# 2_processor.net
KiCad netlist of a schematic drawn in Altium Designer
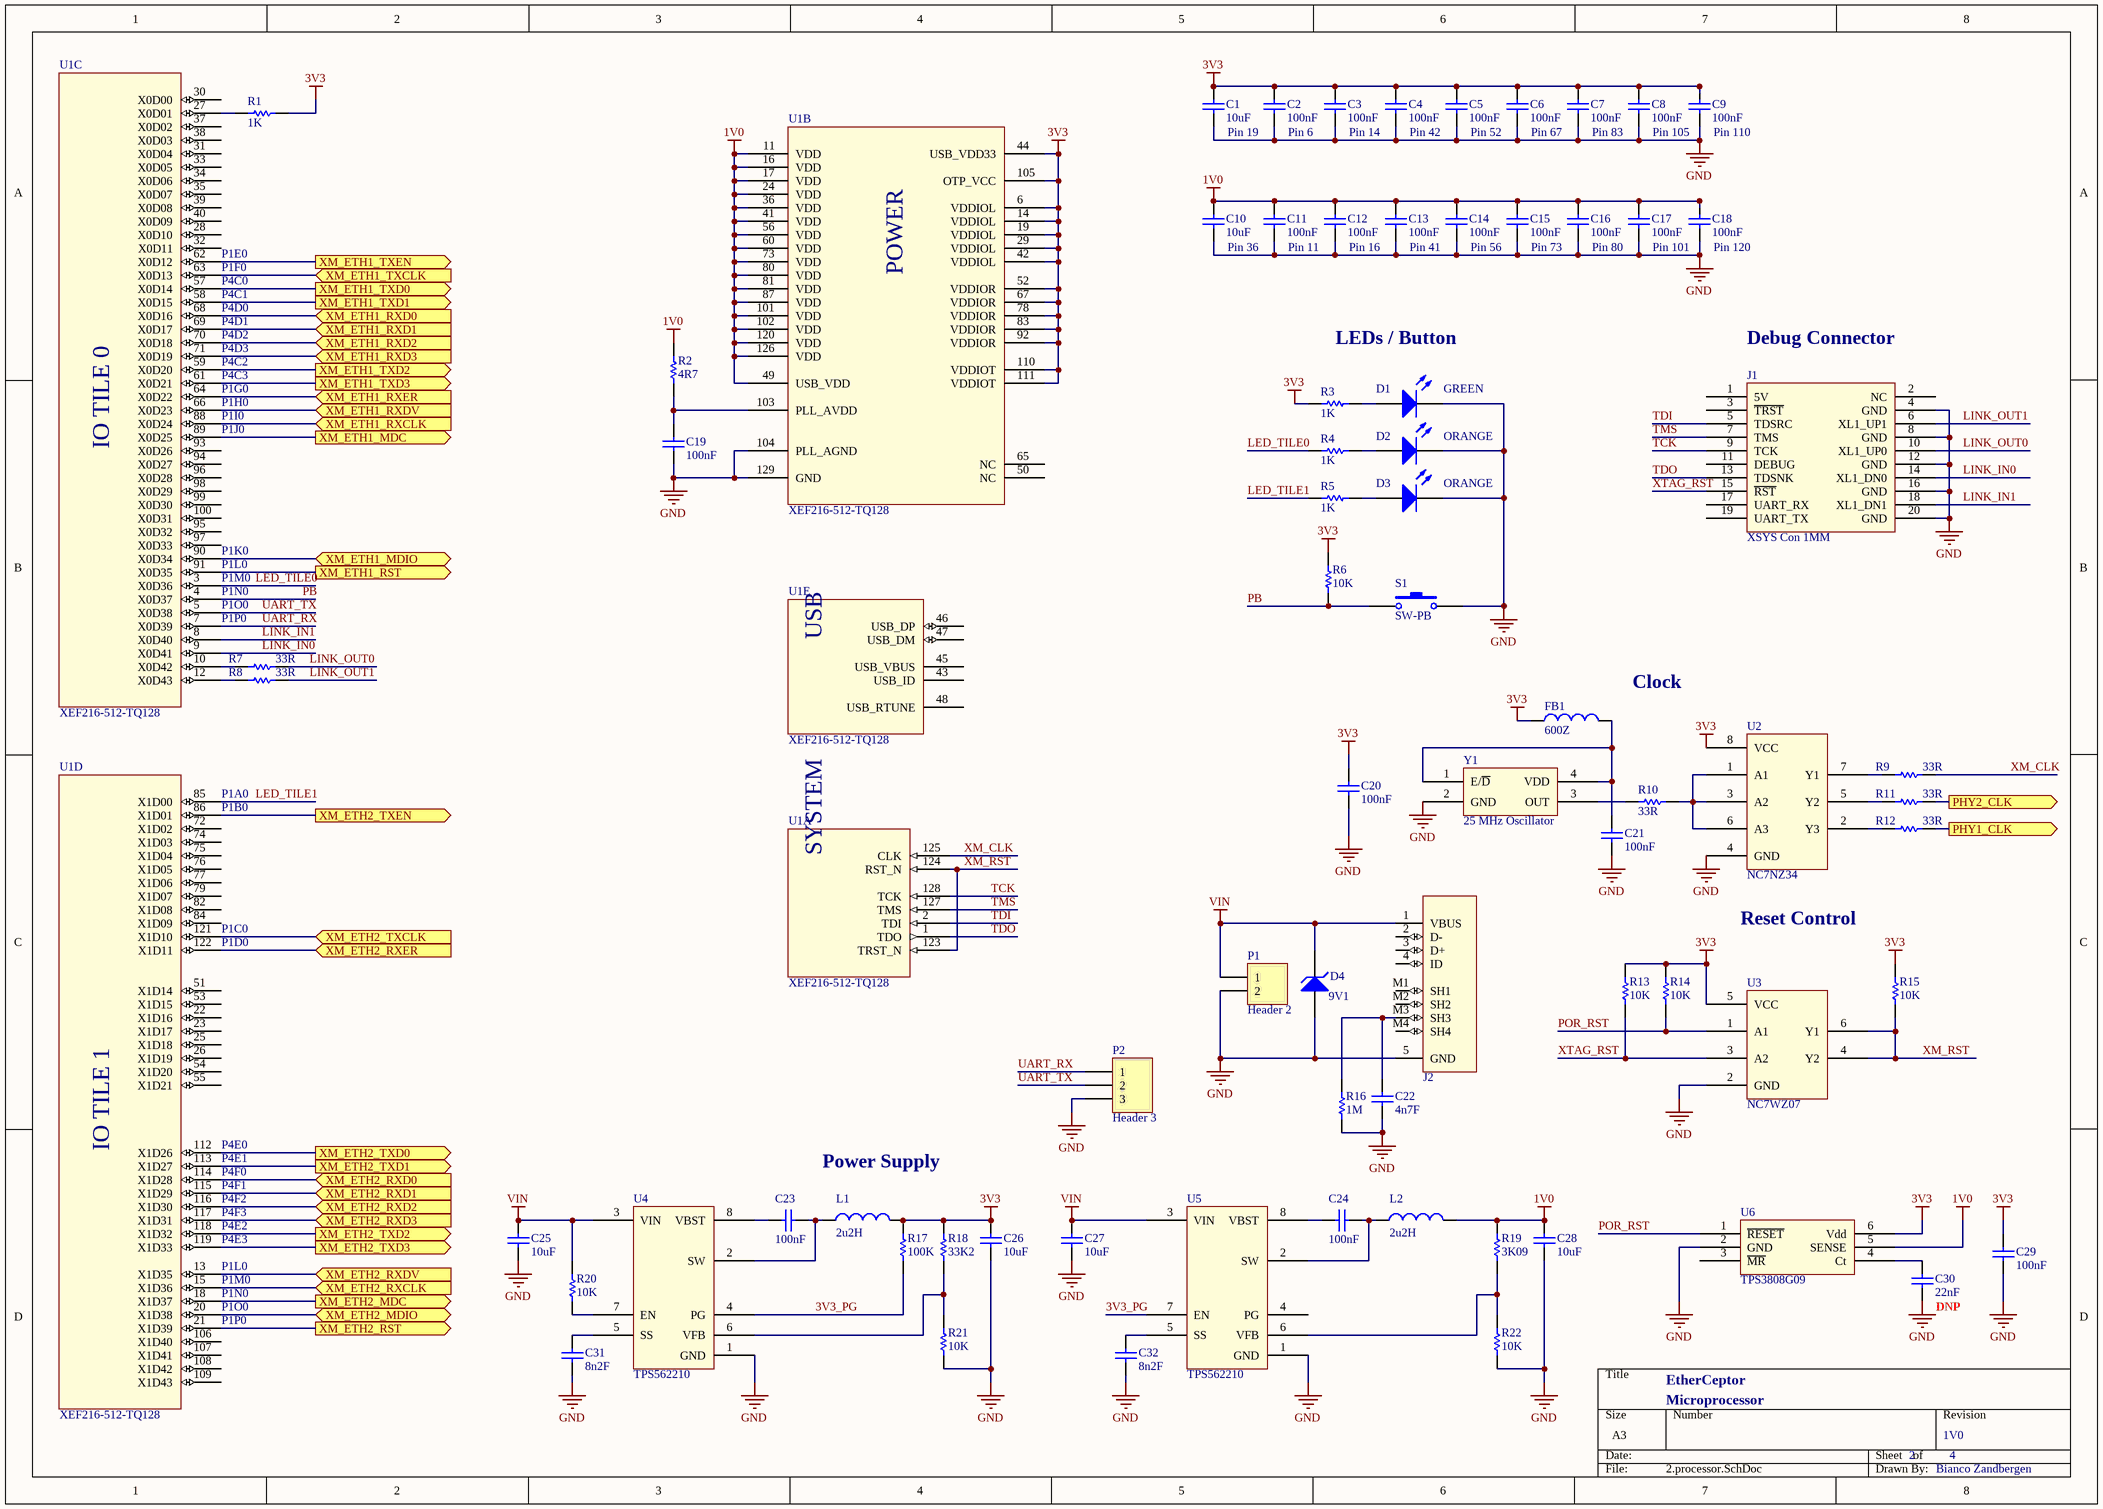
[diagram p0: 2.processor.SchDoc]

(export (version "E")
  (design (tool "Eeschema 10.0.6"))
  (components
    (comp (ref "C1")
      (value "Pin 19")
      (footprint "1608[0603]_CAP2")
      (description "Capacitor")
      (fields (field (name "ALTIUM_VALUE") "10uF") (field (name "MANUFACTURER") "SAMSUNG"))
      (libsource (lib "etherceptor") (part "Cap"))
    )
    (comp (ref "C2")
      (value "Pin 6")
      (footprint "1005[0402]_CAP2")
      (description "Capacitor")
      (fields (field (name "ALTIUM_VALUE") "100nF") (field (name "MANUFACTURER") "SAMSUNG"))
      (libsource (lib "etherceptor") (part "Cap"))
    )
    (comp (ref "C3")
      (value "Pin 14")
      (footprint "1005[0402]_CAP2")
      (description "Capacitor")
      (fields (field (name "ALTIUM_VALUE") "100nF") (field (name "MANUFACTURER") "SAMSUNG"))
      (libsource (lib "etherceptor") (part "Cap"))
    )
    (comp (ref "C4")
      (value "Pin 42")
      (footprint "1005[0402]_CAP2")
      (description "Capacitor")
      (fields (field (name "ALTIUM_VALUE") "100nF") (field (name "MANUFACTURER") "SAMSUNG"))
      (libsource (lib "etherceptor") (part "Cap"))
    )
    (comp (ref "C5")
      (value "Pin 52")
      (footprint "1005[0402]_CAP2")
      (description "Capacitor")
      (fields (field (name "ALTIUM_VALUE") "100nF") (field (name "MANUFACTURER") "SAMSUNG"))
      (libsource (lib "etherceptor") (part "Cap"))
    )
    (comp (ref "C6")
      (value "Pin 67")
      (footprint "1005[0402]_CAP2")
      (description "Capacitor")
      (fields (field (name "ALTIUM_VALUE") "100nF") (field (name "MANUFACTURER") "SAMSUNG"))
      (libsource (lib "etherceptor") (part "Cap"))
    )
    (comp (ref "C7")
      (value "Pin 83")
      (footprint "1005[0402]_CAP2")
      (description "Capacitor")
      (fields (field (name "ALTIUM_VALUE") "100nF") (field (name "MANUFACTURER") "SAMSUNG"))
      (libsource (lib "etherceptor") (part "Cap"))
    )
    (comp (ref "C8")
      (value "Pin 105")
      (footprint "1005[0402]_CAP2")
      (description "Capacitor")
      (fields (field (name "ALTIUM_VALUE") "100nF") (field (name "MANUFACTURER") "SAMSUNG"))
      (libsource (lib "etherceptor") (part "Cap"))
    )
    (comp (ref "C9")
      (value "Pin 110")
      (footprint "1005[0402]_CAP2")
      (description "Capacitor")
      (fields (field (name "ALTIUM_VALUE") "100nF") (field (name "MANUFACTURER") "SAMSUNG"))
      (libsource (lib "etherceptor") (part "Cap"))
    )
    (comp (ref "C10")
      (value "Pin 36")
      (footprint "1608[0603]_CAP2")
      (description "Capacitor")
      (fields (field (name "ALTIUM_VALUE") "10uF") (field (name "MANUFACTURER") "SAMSUNG"))
      (libsource (lib "etherceptor") (part "Cap"))
    )
    (comp (ref "C11")
      (value "Pin 11")
      (footprint "1005[0402]_CAP2")
      (description "Capacitor")
      (fields (field (name "ALTIUM_VALUE") "100nF") (field (name "MANUFACTURER") "SAMSUNG"))
      (libsource (lib "etherceptor") (part "Cap"))
    )
    (comp (ref "C12")
      (value "Pin 16")
      (footprint "1005[0402]_CAP2")
      (description "Capacitor")
      (fields (field (name "ALTIUM_VALUE") "100nF") (field (name "MANUFACTURER") "SAMSUNG"))
      (libsource (lib "etherceptor") (part "Cap"))
    )
    (comp (ref "C13")
      (value "Pin 41")
      (footprint "1005[0402]_CAP2")
      (description "Capacitor")
      (fields (field (name "ALTIUM_VALUE") "100nF") (field (name "MANUFACTURER") "SAMSUNG"))
      (libsource (lib "etherceptor") (part "Cap"))
    )
    (comp (ref "C14")
      (value "Pin 56")
      (footprint "1005[0402]_CAP2")
      (description "Capacitor")
      (fields (field (name "ALTIUM_VALUE") "100nF") (field (name "MANUFACTURER") "SAMSUNG"))
      (libsource (lib "etherceptor") (part "Cap"))
    )
    (comp (ref "C15")
      (value "Pin 73")
      (footprint "1005[0402]_CAP2")
      (description "Capacitor")
      (fields (field (name "ALTIUM_VALUE") "100nF") (field (name "MANUFACTURER") "SAMSUNG"))
      (libsource (lib "etherceptor") (part "Cap"))
    )
    (comp (ref "C16")
      (value "Pin 80")
      (footprint "1005[0402]_CAP2")
      (description "Capacitor")
      (fields (field (name "ALTIUM_VALUE") "100nF") (field (name "MANUFACTURER") "SAMSUNG"))
      (libsource (lib "etherceptor") (part "Cap"))
    )
    (comp (ref "C17")
      (value "Pin 101")
      (footprint "1005[0402]_CAP2")
      (description "Capacitor")
      (fields (field (name "ALTIUM_VALUE") "100nF") (field (name "MANUFACTURER") "SAMSUNG"))
      (libsource (lib "etherceptor") (part "Cap"))
    )
    (comp (ref "C18")
      (value "Pin 120")
      (footprint "1005[0402]_CAP2")
      (description "Capacitor")
      (fields (field (name "ALTIUM_VALUE") "100nF") (field (name "MANUFACTURER") "SAMSUNG"))
      (libsource (lib "etherceptor") (part "Cap"))
    )
    (comp (ref "C19")
      (value "100nF")
      (footprint "1005[0402]_CAP2")
      (description "Capacitor")
      (fields (field (name "MANUFACTURER") "SAMSUNG") (field (name "Comment") "Cap"))
      (libsource (lib "etherceptor") (part "Cap"))
    )
    (comp (ref "C20")
      (value "100nF")
      (footprint "1005[0402]_CAP2")
      (description "Capacitor")
      (fields (field (name "MANUFACTURER") "SAMSUNG") (field (name "Comment") "Cap"))
      (libsource (lib "etherceptor") (part "Cap"))
    )
    (comp (ref "C21")
      (value "100nF")
      (footprint "1005[0402]_CAP2")
      (description "Capacitor")
      (fields (field (name "MANUFACTURER") "SAMSUNG") (field (name "Comment") "Cap"))
      (libsource (lib "etherceptor") (part "Cap"))
    )
    (comp (ref "C22")
      (value "4n7F")
      (footprint "1005[0402]_CAP2")
      (description "Capacitor")
      (fields (field (name "MANUFACTURER") "SAMSUNG") (field (name "Comment") "Cap"))
      (libsource (lib "etherceptor") (part "Cap"))
    )
    (comp (ref "C23")
      (value "100nF")
      (footprint "1005[0402]_CAP2")
      (description "Capacitor")
      (fields (field (name "MANUFACTURER") "SAMSUNG") (field (name "Comment") "Cap"))
      (libsource (lib "etherceptor") (part "Cap"))
    )
    (comp (ref "C24")
      (value "100nF")
      (footprint "1005[0402]_CAP2")
      (description "Capacitor")
      (fields (field (name "MANUFACTURER") "SAMSUNG") (field (name "Comment") "Cap"))
      (libsource (lib "etherceptor") (part "Cap"))
    )
    (comp (ref "C25")
      (value "10uF")
      (footprint "1608[0603]_CAP2")
      (description "Capacitor")
      (fields (field (name "MANUFACTURER") "SAMSUNG") (field (name "Comment") "Cap"))
      (libsource (lib "etherceptor") (part "Cap"))
    )
    (comp (ref "C26")
      (value "10uF")
      (footprint "1608[0603]_CAP2")
      (description "Capacitor")
      (fields (field (name "MANUFACTURER") "SAMSUNG") (field (name "Comment") "Cap"))
      (libsource (lib "etherceptor") (part "Cap"))
    )
    (comp (ref "C27")
      (value "10uF")
      (footprint "1608[0603]_CAP2")
      (description "Capacitor")
      (fields (field (name "MANUFACTURER") "SAMSUNG") (field (name "Comment") "Cap"))
      (libsource (lib "etherceptor") (part "Cap"))
    )
    (comp (ref "C28")
      (value "10uF")
      (footprint "1608[0603]_CAP2")
      (description "Capacitor")
      (fields (field (name "MANUFACTURER") "SAMSUNG") (field (name "Comment") "Cap"))
      (libsource (lib "etherceptor") (part "Cap"))
    )
    (comp (ref "C29")
      (value "100nF")
      (footprint "1005[0402]_CAP2")
      (description "Capacitor")
      (fields (field (name "MANUFACTURER") "SAMSUNG") (field (name "Comment") "Cap"))
      (libsource (lib "etherceptor") (part "Cap"))
    )
    (comp (ref "C30")
      (value "22nF")
      (footprint "1005[0402]_CAP2")
      (description "Capacitor")
      (fields (field (name "MANUFACTURER") "SAMSUNG") (field (name "Comment") "Cap"))
      (libsource (lib "etherceptor") (part "Cap"))
    )
    (comp (ref "C31")
      (value "8n2F")
      (footprint "1005[0402]_CAP2")
      (description "Capacitor")
      (fields (field (name "MANUFACTURER") "SAMSUNG") (field (name "Comment") "Cap"))
      (libsource (lib "etherceptor") (part "Cap"))
    )
    (comp (ref "C32")
      (value "8n2F")
      (footprint "1005[0402]_CAP2")
      (description "Capacitor")
      (fields (field (name "MANUFACTURER") "SAMSUNG") (field (name "Comment") "Cap"))
      (libsource (lib "etherceptor") (part "Cap"))
    )
    (comp (ref "D1")
      (value "GREEN")
      (footprint "1608[0603]_LED")
      (description "SMD LED")
      (fields (field (name "MANUFACTURER") "BROADCOM") (field (name "Comment") "LED3"))
      (libsource (lib "etherceptor") (part "LED3"))
    )
    (comp (ref "D2")
      (value "ORANGE")
      (footprint "1608[0603]_LED")
      (description "SMD LED")
      (fields (field (name "MANUFACTURER") "BROADCOM") (field (name "Comment") "LED3"))
      (libsource (lib "etherceptor") (part "LED3"))
    )
    (comp (ref "D3")
      (value "ORANGE")
      (footprint "1608[0603]_LED")
      (description "SMD LED")
      (fields (field (name "MANUFACTURER") "BROADCOM") (field (name "Comment") "LED3"))
      (libsource (lib "etherceptor") (part "LED3"))
    )
    (comp (ref "D4")
      (value "9V1")
      (footprint "SOD123F")
      (description "Zener Diode")
      (fields (field (name "MANUFACTURER") "NEXPERIA"))
      (libsource (lib "etherceptor") (part "Diode Zener"))
    )
    (comp (ref "FB1")
      (value "600Z")
      (footprint "1005[0402]_FB2")
      (description "Ferrite Bead")
      (fields (field (name "MANUFACTURER") "MURATA"))
      (libsource (lib "etherceptor") (part "Ferrite Bead"))
    )
    (comp (ref "J1")
      (value "XSYS Con 1MM")
      (footprint "M40-3201045R")
      (description "XTAG2 Connector")
      (fields (field (name "MANUFACTURER") "HARWIN"))
      (libsource (lib "etherceptor") (part "XTAG2_CON"))
    )
    (comp (ref "J2")
      (value "Micro-USB B Receptacle")
      (footprint "MOLEX_105017-0001")
      (description "Micro-USB B Receptacle with Flange, Bottom Mount, SMT, Lead-Free")
      (fields (field (name "MP") "47346-0001") (field (name "MF") "Molex"))
      (libsource (lib "etherceptor") (part "Molex Micro-USB 105017-1001"))
    )
    (comp (ref "L1")
      (value "2u2H")
      (footprint "2012[0805]_IND")
      (description "Inductor")
      (fields (field (name "MANUFACTURER") "WURTH"))
      (libsource (lib "etherceptor") (part "Inductor"))
    )
    (comp (ref "L2")
      (value "2u2H")
      (footprint "2012[0805]_IND")
      (description "Inductor")
      (fields (field (name "MANUFACTURER") "WURTH"))
      (libsource (lib "etherceptor") (part "Inductor"))
    )
    (comp (ref "P1")
      (value "Header 2")
      (footprint "HDR1X2")
      (description "Header, 2-Pin")
      (libsource (lib "etherceptor") (part "Header 2"))
    )
    (comp (ref "P2")
      (value "Header 3")
      (footprint "HDR1X3")
      (description "Header, 3-Pin")
      (libsource (lib "etherceptor") (part "Header 3"))
    )
    (comp (ref "R1")
      (value "1K")
      (footprint "1005[0402]_RES2")
      (description "Resistor")
      (fields (field (name "MANUFACTURER") "PANASONIC") (field (name "Comment") "Res"))
      (libsource (lib "etherceptor") (part "Res"))
    )
    (comp (ref "R2")
      (value "4R7")
      (footprint "1005[0402]_RES2")
      (description "Resistor")
      (fields (field (name "MANUFACTURER") "PANASONIC") (field (name "Comment") "Res"))
      (libsource (lib "etherceptor") (part "Res"))
    )
    (comp (ref "R3")
      (value "1K")
      (footprint "1005[0402]_RES2")
      (description "Resistor")
      (fields (field (name "MANUFACTURER") "PANASONIC") (field (name "Comment") "Res"))
      (libsource (lib "etherceptor") (part "Res"))
    )
    (comp (ref "R4")
      (value "1K")
      (footprint "1005[0402]_RES2")
      (description "Resistor")
      (fields (field (name "MANUFACTURER") "PANASONIC") (field (name "Comment") "Res"))
      (libsource (lib "etherceptor") (part "Res"))
    )
    (comp (ref "R5")
      (value "1K")
      (footprint "1005[0402]_RES2")
      (description "Resistor")
      (fields (field (name "MANUFACTURER") "PANASONIC") (field (name "Comment") "Res"))
      (libsource (lib "etherceptor") (part "Res"))
    )
    (comp (ref "R6")
      (value "10K")
      (footprint "1005[0402]_RES2")
      (description "Resistor")
      (fields (field (name "MANUFACTURER") "PANASONIC") (field (name "Comment") "Res"))
      (libsource (lib "etherceptor") (part "Res"))
    )
    (comp (ref "R7")
      (value "33R")
      (footprint "1005[0402]_RES2")
      (description "Resistor")
      (fields (field (name "MANUFACTURER") "PANASONIC") (field (name "Comment") "Res"))
      (libsource (lib "etherceptor") (part "Res"))
    )
    (comp (ref "R8")
      (value "33R")
      (footprint "1005[0402]_RES2")
      (description "Resistor")
      (fields (field (name "MANUFACTURER") "PANASONIC") (field (name "Comment") "Res"))
      (libsource (lib "etherceptor") (part "Res"))
    )
    (comp (ref "R9")
      (value "33R")
      (footprint "1005[0402]_RES2")
      (description "Resistor")
      (fields (field (name "MANUFACTURER") "PANASONIC") (field (name "Comment") "Res"))
      (libsource (lib "etherceptor") (part "Res"))
    )
    (comp (ref "R10")
      (value "33R")
      (footprint "1005[0402]_RES2")
      (description "Resistor")
      (fields (field (name "MANUFACTURER") "PANASONIC") (field (name "Comment") "Res"))
      (libsource (lib "etherceptor") (part "Res"))
    )
    (comp (ref "R11")
      (value "33R")
      (footprint "1005[0402]_RES2")
      (description "Resistor")
      (fields (field (name "MANUFACTURER") "PANASONIC") (field (name "Comment") "Res"))
      (libsource (lib "etherceptor") (part "Res"))
    )
    (comp (ref "R12")
      (value "33R")
      (footprint "1005[0402]_RES2")
      (description "Resistor")
      (fields (field (name "MANUFACTURER") "PANASONIC") (field (name "Comment") "Res"))
      (libsource (lib "etherceptor") (part "Res"))
    )
    (comp (ref "R13")
      (value "10K")
      (footprint "1005[0402]_RES2")
      (description "Resistor")
      (fields (field (name "MANUFACTURER") "PANASONIC") (field (name "Comment") "Res"))
      (libsource (lib "etherceptor") (part "Res"))
    )
    (comp (ref "R14")
      (value "10K")
      (footprint "1005[0402]_RES2")
      (description "Resistor")
      (fields (field (name "MANUFACTURER") "PANASONIC") (field (name "Comment") "Res"))
      (libsource (lib "etherceptor") (part "Res"))
    )
    (comp (ref "R15")
      (value "10K")
      (footprint "1005[0402]_RES2")
      (description "Resistor")
      (fields (field (name "MANUFACTURER") "PANASONIC") (field (name "Comment") "Res"))
      (libsource (lib "etherceptor") (part "Res"))
    )
    (comp (ref "R16")
      (value "1M")
      (footprint "1005[0402]_RES2")
      (description "Resistor")
      (fields (field (name "MANUFACTURER") "PANASONIC") (field (name "Comment") "Res"))
      (libsource (lib "etherceptor") (part "Res"))
    )
    (comp (ref "R17")
      (value "100K")
      (footprint "1005[0402]_RES2")
      (description "Resistor")
      (fields (field (name "MANUFACTURER") "PANASONIC") (field (name "Comment") "Res"))
      (libsource (lib "etherceptor") (part "Res"))
    )
    (comp (ref "R18")
      (value "33K2")
      (footprint "1005[0402]_RES2")
      (description "Resistor")
      (fields (field (name "MANUFACTURER") "PANASONIC") (field (name "Comment") "Res"))
      (libsource (lib "etherceptor") (part "Res"))
    )
    (comp (ref "R19")
      (value "3K09")
      (footprint "1005[0402]_RES2")
      (description "Resistor")
      (fields (field (name "MANUFACTURER") "PANASONIC") (field (name "Comment") "Res"))
      (libsource (lib "etherceptor") (part "Res"))
    )
    (comp (ref "R20")
      (value "10K")
      (footprint "1005[0402]_RES2")
      (description "Resistor")
      (fields (field (name "MANUFACTURER") "PANASONIC") (field (name "Comment") "Res"))
      (libsource (lib "etherceptor") (part "Res"))
    )
    (comp (ref "R21")
      (value "10K")
      (footprint "1005[0402]_RES2")
      (description "Resistor")
      (fields (field (name "MANUFACTURER") "PANASONIC") (field (name "Comment") "Res"))
      (libsource (lib "etherceptor") (part "Res"))
    )
    (comp (ref "R22")
      (value "10K")
      (footprint "1005[0402]_RES2")
      (description "Resistor")
      (fields (field (name "MANUFACTURER") "PANASONIC") (field (name "Comment") "Res"))
      (libsource (lib "etherceptor") (part "Res"))
    )
    (comp (ref "S1")
      (value "SW-PB")
      (footprint "TACTILE_SW_6035_1")
      (description "Switch")
      (fields (field (name "MANUFACTURER") "PANASONIC"))
      (libsource (lib "etherceptor") (part "SW-PB"))
    )
    (comp (ref "U1")
      (value "XEF216-512-TQ128")
      (footprint "XMOS_LQFP_128_XEF216_512")
      (description "XMOS xCORE200 Processor")
      (fields
        (field (name "MANUFACTURER") "XMOS")
        (field (name "MANUFACTURER PART NUMBER") "XE216-512-TQ128")
      )
      (libsource (lib "etherceptor") (part "XEF216-512-TQ128"))
    )
    (comp (ref "U2")
      (value "NC7NZ34")
      (footprint "US8")
      (description "Tripple Buffer")
      (fields (field (name "MANUFACTURER") "ON SEMICONDUCTOR"))
      (libsource (lib "etherceptor") (part "NC7NZ34"))
    )
    (comp (ref "U3")
      (value "NC7WZ07")
      (footprint "SOT363-6M_SC70")
      (description "Dual Buffer (open drain output)")
      (fields (field (name "MANUFACTURER") "ON SEMICONDUCTOR"))
      (libsource (lib "etherceptor") (part "NC7WZ07"))
    )
    (comp (ref "U4")
      (value "TPS562210")
      (footprint "SOT-23-8")
      (description "Buck converter")
      (fields (field (name "MANUFACTURER") "TEXAS INSTRUMENTS"))
      (libsource (lib "etherceptor") (part "TPS562210"))
    )
    (comp (ref "U5")
      (value "TPS562210")
      (footprint "SOT-23-8")
      (description "Buck converter")
      (fields (field (name "MANUFACTURER") "TEXAS INSTRUMENTS"))
      (libsource (lib "etherceptor") (part "TPS562210"))
    )
    (comp (ref "U6")
      (value "TPS3808G09")
      (footprint "SOT23-6")
      (description "Power on Reset controller 0.9V")
      (fields (field (name "MANUFACTURER") "TEXAS INSTRUMENTS"))
      (libsource (lib "etherceptor") (part "TPS3808G09"))
    )
    (comp (ref "Y1")
      (value "25 MHz Oscillator")
      (footprint "OSC_32_25")
      (description "Crystal Oscillator")
      (fields (field (name "MANUFACTURER") "ABRACON"))
      (libsource (lib "etherceptor") (part "oscillator"))
    )
  )
  (nets
    (net (code "1") (name "/3V3_PG") (class "Default")
      (node (ref "R17") (pin "1") (pinfunction "1_1") (pintype "passive"))
      (node (ref "U4") (pin "4") (pinfunction "PG_4") (pintype "passive"))
      (node (ref "U5") (pin "7") (pinfunction "EN_7") (pintype "passive"))
    )
    (net (code "2") (name "/LED_TILE0") (class "Default")
      (node (ref "R4") (pin "2") (pinfunction "2_2") (pintype "passive"))
      (node (ref "U1") (pin "3") (pinfunction "X0D36_3") (pintype "bidirectional"))
    )
    (net (code "3") (name "/LED_TILE1") (class "Default")
      (node (ref "R5") (pin "2") (pinfunction "2_2") (pintype "passive"))
      (node (ref "U1") (pin "85") (pinfunction "X1D00_85") (pintype "bidirectional"))
    )
    (net (code "4") (name "/LINK_IN0") (class "Default")
      (node (ref "J1") (pin "14") (pinfunction "XL1_DN0_14") (pintype "passive"))
      (node (ref "U1") (pin "9") (pinfunction "X0D41_9") (pintype "bidirectional"))
    )
    (net (code "5") (name "/LINK_IN1") (class "Default")
      (node (ref "J1") (pin "18") (pinfunction "XL1_DN1_18") (pintype "passive"))
      (node (ref "U1") (pin "8") (pinfunction "X0D40_8") (pintype "bidirectional"))
    )
    (net (code "6") (name "/LINK_OUT0") (class "Default")
      (node (ref "J1") (pin "10") (pinfunction "XL1_UP0_10") (pintype "passive"))
      (node (ref "R7") (pin "1") (pinfunction "1_1") (pintype "passive"))
    )
    (net (code "7") (name "/LINK_OUT1") (class "Default")
      (node (ref "J1") (pin "6") (pinfunction "XL1_UP1_6") (pintype "passive"))
      (node (ref "R8") (pin "1") (pinfunction "1_1") (pintype "passive"))
    )
    (net (code "8") (name "/PB") (class "Default")
      (node (ref "R6") (pin "1") (pinfunction "1_1") (pintype "passive"))
      (node (ref "S1") (pin "1") (pinfunction "1_1") (pintype "passive"))
      (node (ref "U1") (pin "4") (pinfunction "X0D37_4") (pintype "bidirectional"))
    )
    (net (code "9") (name "/PHY1_CLK") (class "Default")
      (node (ref "R12") (pin "1") (pinfunction "1_1") (pintype "passive"))
    )
    (net (code "10") (name "/PHY2_CLK") (class "Default")
      (node (ref "R11") (pin "1") (pinfunction "1_1") (pintype "passive"))
    )
    (net (code "11") (name "/POR_RST") (class "Default")
      (node (ref "R14") (pin "1") (pinfunction "1_1") (pintype "passive"))
      (node (ref "U3") (pin "1") (pinfunction "A1_1") (pintype "passive"))
      (node (ref "U6") (pin "1") (pinfunction "~{RESET}_1") (pintype "passive"))
    )
    (net (code "12") (name "/TCK") (class "Default")
      (node (ref "J1") (pin "9") (pinfunction "TCK_9") (pintype "passive"))
      (node (ref "U1") (pin "128") (pinfunction "TCK_128") (pintype "input"))
    )
    (net (code "13") (name "/TDI") (class "Default")
      (node (ref "J1") (pin "5") (pinfunction "TDSRC_5") (pintype "passive"))
      (node (ref "U1") (pin "2") (pinfunction "TDI_2") (pintype "input"))
    )
    (net (code "14") (name "/TDO") (class "Default")
      (node (ref "J1") (pin "13") (pinfunction "TDSNK_13") (pintype "passive"))
      (node (ref "U1") (pin "1") (pinfunction "TDO_1") (pintype "output"))
    )
    (net (code "15") (name "/TMS") (class "Default")
      (node (ref "J1") (pin "7") (pinfunction "TMS_7") (pintype "passive"))
      (node (ref "U1") (pin "127") (pinfunction "TMS_127") (pintype "input"))
    )
    (net (code "16") (name "/UART_RX") (class "Default")
      (node (ref "P2") (pin "1") (pinfunction "1_1") (pintype "passive"))
      (node (ref "U1") (pin "7") (pinfunction "X0D39_7") (pintype "bidirectional"))
    )
    (net (code "17") (name "/UART_TX") (class "Default")
      (node (ref "P2") (pin "2") (pinfunction "2_2") (pintype "passive"))
      (node (ref "U1") (pin "5") (pinfunction "X0D38_5") (pintype "bidirectional"))
    )
    (net (code "18") (name "/XM_CLK") (class "Default")
      (node (ref "R9") (pin "1") (pinfunction "1_1") (pintype "passive"))
      (node (ref "U1") (pin "125") (pinfunction "CLK_125") (pintype "input"))
    )
    (net (code "19") (name "/XM_ETH1_MDC") (class "Default")
      (node (ref "U1") (pin "89") (pinfunction "X0D25_89") (pintype "bidirectional"))
    )
    (net (code "20") (name "/XM_ETH1_MDIO") (class "Default")
      (node (ref "U1") (pin "90") (pinfunction "X0D34_90") (pintype "bidirectional"))
    )
    (net (code "21") (name "/XM_ETH1_RST") (class "Default")
      (node (ref "U1") (pin "91") (pinfunction "X0D35_91") (pintype "bidirectional"))
    )
    (net (code "22") (name "/XM_ETH1_RXCLK") (class "Default")
      (node (ref "U1") (pin "88") (pinfunction "X0D24_88") (pintype "bidirectional"))
    )
    (net (code "23") (name "/XM_ETH1_RXD0") (class "Default")
      (node (ref "U1") (pin "68") (pinfunction "X0D16_68") (pintype "bidirectional"))
    )
    (net (code "24") (name "/XM_ETH1_RXD1") (class "Default")
      (node (ref "U1") (pin "69") (pinfunction "X0D17_69") (pintype "bidirectional"))
    )
    (net (code "25") (name "/XM_ETH1_RXD2") (class "Default")
      (node (ref "U1") (pin "70") (pinfunction "X0D18_70") (pintype "bidirectional"))
    )
    (net (code "26") (name "/XM_ETH1_RXD3") (class "Default")
      (node (ref "U1") (pin "71") (pinfunction "X0D19_71") (pintype "bidirectional"))
    )
    (net (code "27") (name "/XM_ETH1_RXDV") (class "Default")
      (node (ref "U1") (pin "66") (pinfunction "X0D23_66") (pintype "bidirectional"))
    )
    (net (code "28") (name "/XM_ETH1_RXER") (class "Default")
      (node (ref "U1") (pin "64") (pinfunction "X0D22_64") (pintype "bidirectional"))
    )
    (net (code "29") (name "/XM_ETH1_TXCLK") (class "Default")
      (node (ref "U1") (pin "63") (pinfunction "X0D13_63") (pintype "bidirectional"))
    )
    (net (code "30") (name "/XM_ETH1_TXD0") (class "Default")
      (node (ref "U1") (pin "57") (pinfunction "X0D14_57") (pintype "bidirectional"))
    )
    (net (code "31") (name "/XM_ETH1_TXD1") (class "Default")
      (node (ref "U1") (pin "58") (pinfunction "X0D15_58") (pintype "bidirectional"))
    )
    (net (code "32") (name "/XM_ETH1_TXD2") (class "Default")
      (node (ref "U1") (pin "59") (pinfunction "X0D20_59") (pintype "bidirectional"))
    )
    (net (code "33") (name "/XM_ETH1_TXD3") (class "Default")
      (node (ref "U1") (pin "61") (pinfunction "X0D21_61") (pintype "bidirectional"))
    )
    (net (code "34") (name "/XM_ETH1_TXEN") (class "Default")
      (node (ref "U1") (pin "62") (pinfunction "X0D12_62") (pintype "bidirectional"))
    )
    (net (code "35") (name "/XM_ETH2_MDC") (class "Default")
      (node (ref "U1") (pin "18") (pinfunction "X1D37_18") (pintype "bidirectional"))
    )
    (net (code "36") (name "/XM_ETH2_MDIO") (class "Default")
      (node (ref "U1") (pin "20") (pinfunction "X1D38_20") (pintype "bidirectional"))
    )
    (net (code "37") (name "/XM_ETH2_RST") (class "Default")
      (node (ref "U1") (pin "21") (pinfunction "X1D39_21") (pintype "bidirectional"))
    )
    (net (code "38") (name "/XM_ETH2_RXCLK") (class "Default")
      (node (ref "U1") (pin "15") (pinfunction "X1D36_15") (pintype "bidirectional"))
    )
    (net (code "39") (name "/XM_ETH2_RXD0") (class "Default")
      (node (ref "U1") (pin "114") (pinfunction "X1D28_114") (pintype "bidirectional"))
    )
    (net (code "40") (name "/XM_ETH2_RXD1") (class "Default")
      (node (ref "U1") (pin "115") (pinfunction "X1D29_115") (pintype "bidirectional"))
    )
    (net (code "41") (name "/XM_ETH2_RXD2") (class "Default")
      (node (ref "U1") (pin "116") (pinfunction "X1D30_116") (pintype "bidirectional"))
    )
    (net (code "42") (name "/XM_ETH2_RXD3") (class "Default")
      (node (ref "U1") (pin "117") (pinfunction "X1D31_117") (pintype "bidirectional"))
    )
    (net (code "43") (name "/XM_ETH2_RXDV") (class "Default")
      (node (ref "U1") (pin "13") (pinfunction "X1D35_13") (pintype "bidirectional"))
    )
    (net (code "44") (name "/XM_ETH2_RXER") (class "Default")
      (node (ref "U1") (pin "122") (pinfunction "X1D11_122") (pintype "bidirectional"))
    )
    (net (code "45") (name "/XM_ETH2_TXCLK") (class "Default")
      (node (ref "U1") (pin "121") (pinfunction "X1D10_121") (pintype "bidirectional"))
    )
    (net (code "46") (name "/XM_ETH2_TXD0") (class "Default")
      (node (ref "U1") (pin "112") (pinfunction "X1D26_112") (pintype "bidirectional"))
    )
    (net (code "47") (name "/XM_ETH2_TXD1") (class "Default")
      (node (ref "U1") (pin "113") (pinfunction "X1D27_113") (pintype "bidirectional"))
    )
    (net (code "48") (name "/XM_ETH2_TXD2") (class "Default")
      (node (ref "U1") (pin "118") (pinfunction "X1D32_118") (pintype "bidirectional"))
    )
    (net (code "49") (name "/XM_ETH2_TXD3") (class "Default")
      (node (ref "U1") (pin "119") (pinfunction "X1D33_119") (pintype "bidirectional"))
    )
    (net (code "50") (name "/XM_ETH2_TXEN") (class "Default")
      (node (ref "U1") (pin "86") (pinfunction "X1D01_86") (pintype "bidirectional"))
    )
    (net (code "51") (name "/XM_RST") (class "Default")
      (node (ref "R15") (pin "1") (pinfunction "1_1") (pintype "passive"))
      (node (ref "U1") (pin "123") (pinfunction "TRST_N_123") (pintype "input"))
      (node (ref "U1") (pin "124") (pinfunction "RST_N_124") (pintype "input"))
      (node (ref "U3") (pin "4") (pinfunction "Y2_4") (pintype "passive"))
      (node (ref "U3") (pin "6") (pinfunction "Y1_6") (pintype "passive"))
    )
    (net (code "52") (name "/XTAG_RST") (class "Default")
      (node (ref "J1") (pin "15") (pinfunction "~{RST}_15") (pintype "passive"))
      (node (ref "R13") (pin "1") (pinfunction "1_1") (pintype "passive"))
      (node (ref "U3") (pin "3") (pinfunction "A2_3") (pintype "passive"))
    )
    (net (code "53") (name "1V0") (class "Default")
      (node (ref "C10") (pin "2") (pinfunction "2_2") (pintype "passive"))
      (node (ref "C11") (pin "2") (pinfunction "2_2") (pintype "passive"))
      (node (ref "C12") (pin "2") (pinfunction "2_2") (pintype "passive"))
      (node (ref "C13") (pin "2") (pinfunction "2_2") (pintype "passive"))
      (node (ref "C14") (pin "2") (pinfunction "2_2") (pintype "passive"))
      (node (ref "C15") (pin "2") (pinfunction "2_2") (pintype "passive"))
      (node (ref "C16") (pin "2") (pinfunction "2_2") (pintype "passive"))
      (node (ref "C17") (pin "2") (pinfunction "2_2") (pintype "passive"))
      (node (ref "C18") (pin "2") (pinfunction "2_2") (pintype "passive"))
      (node (ref "C28") (pin "2") (pinfunction "2_2") (pintype "passive"))
      (node (ref "L2") (pin "2") (pinfunction "2_2") (pintype "passive"))
      (node (ref "R19") (pin "2") (pinfunction "2_2") (pintype "passive"))
      (node (ref "R2") (pin "2") (pinfunction "2_2") (pintype "passive"))
      (node (ref "U1") (pin "101") (pinfunction "VDD_101") (pintype "power_in"))
      (node (ref "U1") (pin "102") (pinfunction "VDD_102") (pintype "power_in"))
      (node (ref "U1") (pin "11") (pinfunction "VDD_11") (pintype "power_in"))
      (node (ref "U1") (pin "120") (pinfunction "VDD_120") (pintype "power_in"))
      (node (ref "U1") (pin "126") (pinfunction "VDD_126") (pintype "power_in"))
      (node (ref "U1") (pin "16") (pinfunction "VDD_16") (pintype "power_in"))
      (node (ref "U1") (pin "17") (pinfunction "VDD_17") (pintype "power_in"))
      (node (ref "U1") (pin "24") (pinfunction "VDD_24") (pintype "power_in"))
      (node (ref "U1") (pin "36") (pinfunction "VDD_36") (pintype "power_in"))
      (node (ref "U1") (pin "41") (pinfunction "VDD_41") (pintype "power_in"))
      (node (ref "U1") (pin "49") (pinfunction "USB_VDD_49") (pintype "power_in"))
      (node (ref "U1") (pin "56") (pinfunction "VDD_56") (pintype "power_in"))
      (node (ref "U1") (pin "60") (pinfunction "VDD_60") (pintype "power_in"))
      (node (ref "U1") (pin "73") (pinfunction "VDD_73") (pintype "power_in"))
      (node (ref "U1") (pin "80") (pinfunction "VDD_80") (pintype "power_in"))
      (node (ref "U1") (pin "81") (pinfunction "VDD_81") (pintype "power_in"))
      (node (ref "U1") (pin "87") (pinfunction "VDD_87") (pintype "power_in"))
      (node (ref "U6") (pin "5") (pinfunction "SENSE_5") (pintype "passive"))
    )
    (net (code "54") (name "3V3") (class "Default")
      (node (ref "C1") (pin "2") (pinfunction "2_2") (pintype "passive"))
      (node (ref "C2") (pin "2") (pinfunction "2_2") (pintype "passive"))
      (node (ref "C20") (pin "2") (pinfunction "2_2") (pintype "passive"))
      (node (ref "C26") (pin "2") (pinfunction "2_2") (pintype "passive"))
      (node (ref "C29") (pin "2") (pinfunction "2_2") (pintype "passive"))
      (node (ref "C3") (pin "2") (pinfunction "2_2") (pintype "passive"))
      (node (ref "C4") (pin "2") (pinfunction "2_2") (pintype "passive"))
      (node (ref "C5") (pin "2") (pinfunction "2_2") (pintype "passive"))
      (node (ref "C6") (pin "2") (pinfunction "2_2") (pintype "passive"))
      (node (ref "C7") (pin "2") (pinfunction "2_2") (pintype "passive"))
      (node (ref "C8") (pin "2") (pinfunction "2_2") (pintype "passive"))
      (node (ref "C9") (pin "2") (pinfunction "2_2") (pintype "passive"))
      (node (ref "FB1") (pin "1") (pinfunction "1_1") (pintype "passive"))
      (node (ref "L1") (pin "2") (pinfunction "2_2") (pintype "passive"))
      (node (ref "R1") (pin "2") (pinfunction "2_2") (pintype "passive"))
      (node (ref "R13") (pin "2") (pinfunction "2_2") (pintype "passive"))
      (node (ref "R14") (pin "2") (pinfunction "2_2") (pintype "passive"))
      (node (ref "R15") (pin "2") (pinfunction "2_2") (pintype "passive"))
      (node (ref "R17") (pin "2") (pinfunction "2_2") (pintype "passive"))
      (node (ref "R18") (pin "2") (pinfunction "2_2") (pintype "passive"))
      (node (ref "R3") (pin "2") (pinfunction "2_2") (pintype "passive"))
      (node (ref "R6") (pin "2") (pinfunction "2_2") (pintype "passive"))
      (node (ref "U1") (pin "105") (pinfunction "OTP_VCC_105") (pintype "power_in"))
      (node (ref "U1") (pin "110") (pinfunction "VDDIOT_110") (pintype "power_in"))
      (node (ref "U1") (pin "111") (pinfunction "VDDIOT_111") (pintype "power_in"))
      (node (ref "U1") (pin "14") (pinfunction "VDDIOL_14") (pintype "power_in"))
      (node (ref "U1") (pin "19") (pinfunction "VDDIOL_19") (pintype "power_in"))
      (node (ref "U1") (pin "29") (pinfunction "VDDIOL_29") (pintype "power_in"))
      (node (ref "U1") (pin "42") (pinfunction "VDDIOL_42") (pintype "power_in"))
      (node (ref "U1") (pin "44") (pinfunction "USB_VDD33_44") (pintype "power_in"))
      (node (ref "U1") (pin "52") (pinfunction "VDDIOR_52") (pintype "power_in"))
      (node (ref "U1") (pin "6") (pinfunction "VDDIOL_6") (pintype "power_in"))
      (node (ref "U1") (pin "67") (pinfunction "VDDIOR_67") (pintype "power_in"))
      (node (ref "U1") (pin "78") (pinfunction "VDDIOR_78") (pintype "power_in"))
      (node (ref "U1") (pin "83") (pinfunction "VDDIOR_83") (pintype "power_in"))
      (node (ref "U1") (pin "92") (pinfunction "VDDIOR_92") (pintype "power_in"))
      (node (ref "U2") (pin "8") (pinfunction "VCC_8") (pintype "passive"))
      (node (ref "U3") (pin "5") (pinfunction "VCC_5") (pintype "passive"))
      (node (ref "U6") (pin "6") (pinfunction "Vdd_6") (pintype "passive"))
    )
    (net (code "55") (name "GND") (class "Default")
      (node (ref "C1") (pin "1") (pinfunction "1_1") (pintype "passive"))
      (node (ref "C10") (pin "1") (pinfunction "1_1") (pintype "passive"))
      (node (ref "C11") (pin "1") (pinfunction "1_1") (pintype "passive"))
      (node (ref "C12") (pin "1") (pinfunction "1_1") (pintype "passive"))
      (node (ref "C13") (pin "1") (pinfunction "1_1") (pintype "passive"))
      (node (ref "C14") (pin "1") (pinfunction "1_1") (pintype "passive"))
      (node (ref "C15") (pin "1") (pinfunction "1_1") (pintype "passive"))
      (node (ref "C16") (pin "1") (pinfunction "1_1") (pintype "passive"))
      (node (ref "C17") (pin "1") (pinfunction "1_1") (pintype "passive"))
      (node (ref "C18") (pin "1") (pinfunction "1_1") (pintype "passive"))
      (node (ref "C19") (pin "1") (pinfunction "1_1") (pintype "passive"))
      (node (ref "C2") (pin "1") (pinfunction "1_1") (pintype "passive"))
      (node (ref "C20") (pin "1") (pinfunction "1_1") (pintype "passive"))
      (node (ref "C21") (pin "1") (pinfunction "1_1") (pintype "passive"))
      (node (ref "C22") (pin "1") (pinfunction "1_1") (pintype "passive"))
      (node (ref "C25") (pin "1") (pinfunction "1_1") (pintype "passive"))
      (node (ref "C26") (pin "1") (pinfunction "1_1") (pintype "passive"))
      (node (ref "C27") (pin "1") (pinfunction "1_1") (pintype "passive"))
      (node (ref "C28") (pin "1") (pinfunction "1_1") (pintype "passive"))
      (node (ref "C29") (pin "1") (pinfunction "1_1") (pintype "passive"))
      (node (ref "C3") (pin "1") (pinfunction "1_1") (pintype "passive"))
      (node (ref "C30") (pin "1") (pinfunction "1_1") (pintype "passive"))
      (node (ref "C31") (pin "1") (pinfunction "1_1") (pintype "passive"))
      (node (ref "C32") (pin "1") (pinfunction "1_1") (pintype "passive"))
      (node (ref "C4") (pin "1") (pinfunction "1_1") (pintype "passive"))
      (node (ref "C5") (pin "1") (pinfunction "1_1") (pintype "passive"))
      (node (ref "C6") (pin "1") (pinfunction "1_1") (pintype "passive"))
      (node (ref "C7") (pin "1") (pinfunction "1_1") (pintype "passive"))
      (node (ref "C8") (pin "1") (pinfunction "1_1") (pintype "passive"))
      (node (ref "C9") (pin "1") (pinfunction "1_1") (pintype "passive"))
      (node (ref "D1") (pin "2") (pinfunction "K_2") (pintype "passive"))
      (node (ref "D2") (pin "2") (pinfunction "K_2") (pintype "passive"))
      (node (ref "D3") (pin "2") (pinfunction "K_2") (pintype "passive"))
      (node (ref "D4") (pin "1") (pinfunction "A_1") (pintype "passive"))
      (node (ref "J1") (pin "12") (pinfunction "GND_12") (pintype "passive"))
      (node (ref "J1") (pin "16") (pinfunction "GND_16") (pintype "passive"))
      (node (ref "J1") (pin "20") (pinfunction "GND_20") (pintype "passive"))
      (node (ref "J1") (pin "4") (pinfunction "GND_4") (pintype "passive"))
      (node (ref "J1") (pin "8") (pinfunction "GND_8") (pintype "passive"))
      (node (ref "J2") (pin "5") (pinfunction "GND_5") (pintype "power_in"))
      (node (ref "P1") (pin "2") (pinfunction "2_2") (pintype "passive"))
      (node (ref "P2") (pin "3") (pinfunction "3_3") (pintype "passive"))
      (node (ref "R16") (pin "1") (pinfunction "1_1") (pintype "passive"))
      (node (ref "R21") (pin "1") (pinfunction "1_1") (pintype "passive"))
      (node (ref "R22") (pin "1") (pinfunction "1_1") (pintype "passive"))
      (node (ref "S1") (pin "2") (pinfunction "2_2") (pintype "passive"))
      (node (ref "U1") (pin "104") (pinfunction "PLL_AGND_104") (pintype "power_in"))
      (node (ref "U1") (pin "129") (pinfunction "GND_129") (pintype "power_in"))
      (node (ref "U2") (pin "4") (pinfunction "GND_4") (pintype "passive"))
      (node (ref "U3") (pin "2") (pinfunction "GND_2") (pintype "passive"))
      (node (ref "U4") (pin "1") (pinfunction "GND_1") (pintype "passive"))
      (node (ref "U5") (pin "1") (pinfunction "GND_1") (pintype "passive"))
      (node (ref "U6") (pin "2") (pinfunction "GND_2") (pintype "passive"))
      (node (ref "Y1") (pin "2") (pinfunction "GND_2") (pintype "passive"))
    )
    (net (code "56") (name "Net-(D1-A)") (class "Default")
      (node (ref "D1") (pin "1") (pinfunction "A_1") (pintype "passive"))
      (node (ref "R3") (pin "1") (pinfunction "1_1") (pintype "passive"))
    )
    (net (code "57") (name "Net-(D2-A)") (class "Default")
      (node (ref "D2") (pin "1") (pinfunction "A_1") (pintype "passive"))
      (node (ref "R4") (pin "1") (pinfunction "1_1") (pintype "passive"))
    )
    (net (code "58") (name "Net-(D3-A)") (class "Default")
      (node (ref "D3") (pin "1") (pinfunction "A_1") (pintype "passive"))
      (node (ref "R5") (pin "1") (pinfunction "1_1") (pintype "passive"))
    )
    (net (code "59") (name "Net-(J2-SH3)") (class "Default")
      (node (ref "C22") (pin "2") (pinfunction "2_2") (pintype "passive"))
      (node (ref "J2") (pin "M3") (pinfunction "SH3_M3") (pintype "bidirectional"))
      (node (ref "R16") (pin "2") (pinfunction "2_2") (pintype "passive"))
    )
    (net (code "60") (name "Net-(U1B-PLL_AVDD)") (class "Default")
      (node (ref "C19") (pin "2") (pinfunction "2_2") (pintype "passive"))
      (node (ref "R2") (pin "1") (pinfunction "1_1") (pintype "passive"))
      (node (ref "U1") (pin "103") (pinfunction "PLL_AVDD_103") (pintype "power_in"))
    )
    (net (code "61") (name "Net-(U1C-X0D01)") (class "Default")
      (node (ref "R1") (pin "1") (pinfunction "1_1") (pintype "passive"))
      (node (ref "U1") (pin "27") (pinfunction "X0D01_27") (pintype "bidirectional"))
    )
    (net (code "62") (name "Net-(U1C-X0D42)") (class "Default")
      (node (ref "R7") (pin "2") (pinfunction "2_2") (pintype "passive"))
      (node (ref "U1") (pin "10") (pinfunction "X0D42_10") (pintype "bidirectional"))
    )
    (net (code "63") (name "Net-(U1C-X0D43)") (class "Default")
      (node (ref "R8") (pin "2") (pinfunction "2_2") (pintype "passive"))
      (node (ref "U1") (pin "12") (pinfunction "X0D43_12") (pintype "bidirectional"))
    )
    (net (code "64") (name "Net-(U2-A1)") (class "Default")
      (node (ref "R10") (pin "1") (pinfunction "1_1") (pintype "passive"))
      (node (ref "U2") (pin "1") (pinfunction "A1_1") (pintype "passive"))
      (node (ref "U2") (pin "3") (pinfunction "A2_3") (pintype "passive"))
      (node (ref "U2") (pin "6") (pinfunction "A3_6") (pintype "passive"))
    )
    (net (code "65") (name "Net-(U2-Y1)") (class "Default")
      (node (ref "R9") (pin "2") (pinfunction "2_2") (pintype "passive"))
      (node (ref "U2") (pin "7") (pinfunction "Y1_7") (pintype "passive"))
    )
    (net (code "66") (name "Net-(U2-Y2)") (class "Default")
      (node (ref "R11") (pin "2") (pinfunction "2_2") (pintype "passive"))
      (node (ref "U2") (pin "5") (pinfunction "Y2_5") (pintype "passive"))
    )
    (net (code "67") (name "Net-(U2-Y3)") (class "Default")
      (node (ref "R12") (pin "2") (pinfunction "2_2") (pintype "passive"))
      (node (ref "U2") (pin "2") (pinfunction "Y3_2") (pintype "passive"))
    )
    (net (code "68") (name "Net-(U4-EN)") (class "Default")
      (node (ref "R20") (pin "1") (pinfunction "1_1") (pintype "passive"))
      (node (ref "U4") (pin "7") (pinfunction "EN_7") (pintype "passive"))
    )
    (net (code "69") (name "Net-(U4-SS)") (class "Default")
      (node (ref "C31") (pin "2") (pinfunction "2_2") (pintype "passive"))
      (node (ref "U4") (pin "5") (pinfunction "SS_5") (pintype "passive"))
    )
    (net (code "70") (name "Net-(U4-SW)") (class "Default")
      (node (ref "C23") (pin "2") (pinfunction "2_2") (pintype "passive"))
      (node (ref "L1") (pin "1") (pinfunction "1_1") (pintype "passive"))
      (node (ref "U4") (pin "2") (pinfunction "SW_2") (pintype "passive"))
    )
    (net (code "71") (name "Net-(U4-VBST)") (class "Default")
      (node (ref "C23") (pin "1") (pinfunction "1_1") (pintype "passive"))
      (node (ref "U4") (pin "8") (pinfunction "VBST_8") (pintype "passive"))
    )
    (net (code "72") (name "Net-(U4-VFB)") (class "Default")
      (node (ref "R18") (pin "1") (pinfunction "1_1") (pintype "passive"))
      (node (ref "R21") (pin "2") (pinfunction "2_2") (pintype "passive"))
      (node (ref "U4") (pin "6") (pinfunction "VFB_6") (pintype "passive"))
    )
    (net (code "73") (name "Net-(U5-SS)") (class "Default")
      (node (ref "C32") (pin "2") (pinfunction "2_2") (pintype "passive"))
      (node (ref "U5") (pin "5") (pinfunction "SS_5") (pintype "passive"))
    )
    (net (code "74") (name "Net-(U5-SW)") (class "Default")
      (node (ref "C24") (pin "2") (pinfunction "2_2") (pintype "passive"))
      (node (ref "L2") (pin "1") (pinfunction "1_1") (pintype "passive"))
      (node (ref "U5") (pin "2") (pinfunction "SW_2") (pintype "passive"))
    )
    (net (code "75") (name "Net-(U5-VBST)") (class "Default")
      (node (ref "C24") (pin "1") (pinfunction "1_1") (pintype "passive"))
      (node (ref "U5") (pin "8") (pinfunction "VBST_8") (pintype "passive"))
    )
    (net (code "76") (name "Net-(U5-VFB)") (class "Default")
      (node (ref "R19") (pin "1") (pinfunction "1_1") (pintype "passive"))
      (node (ref "R22") (pin "2") (pinfunction "2_2") (pintype "passive"))
      (node (ref "U5") (pin "6") (pinfunction "VFB_6") (pintype "passive"))
    )
    (net (code "77") (name "Net-(U6-Ct)") (class "Default")
      (node (ref "C30") (pin "2") (pinfunction "2_2") (pintype "passive"))
      (node (ref "U6") (pin "4") (pinfunction "Ct_4") (pintype "passive"))
    )
    (net (code "78") (name "Net-(Y1-E{slash}~{D})") (class "Default")
      (node (ref "C21") (pin "2") (pinfunction "2_2") (pintype "passive"))
      (node (ref "FB1") (pin "2") (pinfunction "2_2") (pintype "passive"))
      (node (ref "Y1") (pin "1") (pinfunction "E/~{D}_1") (pintype "passive"))
      (node (ref "Y1") (pin "4") (pinfunction "VDD_4") (pintype "passive"))
    )
    (net (code "79") (name "Net-(Y1-OUT)") (class "Default")
      (node (ref "R10") (pin "2") (pinfunction "2_2") (pintype "passive"))
      (node (ref "Y1") (pin "3") (pinfunction "OUT_3") (pintype "passive"))
    )
    (net (code "80") (name "VIN") (class "Default")
      (node (ref "C25") (pin "2") (pinfunction "2_2") (pintype "passive"))
      (node (ref "C27") (pin "2") (pinfunction "2_2") (pintype "passive"))
      (node (ref "D4") (pin "2") (pinfunction "K_2") (pintype "passive"))
      (node (ref "J2") (pin "1") (pinfunction "VBUS_1") (pintype "power_in"))
      (node (ref "P1") (pin "1") (pinfunction "1_1") (pintype "passive"))
      (node (ref "R20") (pin "2") (pinfunction "2_2") (pintype "passive"))
      (node (ref "U4") (pin "3") (pinfunction "VIN_3") (pintype "passive"))
      (node (ref "U5") (pin "3") (pinfunction "VIN_3") (pintype "passive"))
    )
    (net (code "81") (name "unconnected-(J1-5V-Pad1)") (class "Default")
      (node (ref "J1") (pin "1") (pinfunction "5V_1") (pintype "passive"))
    )
    (net (code "82") (name "unconnected-(J1-DEBUG-Pad11)") (class "Default")
      (node (ref "J1") (pin "11") (pinfunction "DEBUG_11") (pintype "passive"))
    )
    (net (code "83") (name "unconnected-(J1-NC-Pad2)") (class "Default")
      (node (ref "J1") (pin "2") (pinfunction "NC_2") (pintype "passive"))
    )
    (net (code "84") (name "unconnected-(J1-UART_RX-Pad17)") (class "Default")
      (node (ref "J1") (pin "17") (pinfunction "UART_RX_17") (pintype "passive"))
    )
    (net (code "85") (name "unconnected-(J1-UART_TX-Pad19)") (class "Default")
      (node (ref "J1") (pin "19") (pinfunction "UART_TX_19") (pintype "passive"))
    )
    (net (code "86") (name "unconnected-(J1-~{TRST}-Pad3)") (class "Default")
      (node (ref "J1") (pin "3") (pinfunction "~{TRST}_3") (pintype "passive"))
    )
    (net (code "87") (name "unconnected-(J2-D+-Pad3)") (class "Default")
      (node (ref "J2") (pin "3") (pinfunction "D+_3") (pintype "bidirectional"))
    )
    (net (code "88") (name "unconnected-(J2-D--Pad2)") (class "Default")
      (node (ref "J2") (pin "2") (pinfunction "D-_2") (pintype "bidirectional"))
    )
    (net (code "89") (name "unconnected-(J2-ID-Pad4)") (class "Default")
      (node (ref "J2") (pin "4") (pinfunction "ID_4") (pintype "bidirectional"))
    )
    (net (code "90") (name "unconnected-(J2-SH1-PadM1)") (class "Default")
      (node (ref "J2") (pin "M1") (pinfunction "SH1_M1") (pintype "bidirectional"))
    )
    (net (code "91") (name "unconnected-(J2-SH2-PadM2)") (class "Default")
      (node (ref "J2") (pin "M2") (pinfunction "SH2_M2") (pintype "bidirectional"))
    )
    (net (code "92") (name "unconnected-(J2-SH4-PadM4)") (class "Default")
      (node (ref "J2") (pin "M4") (pinfunction "SH4_M4") (pintype "bidirectional"))
    )
    (net (code "93") (name "unconnected-(U1B-NC-Pad50)") (class "Default")
      (node (ref "U1") (pin "50") (pinfunction "NC_50") (pintype "passive"))
    )
    (net (code "94") (name "unconnected-(U1B-NC-Pad65)") (class "Default")
      (node (ref "U1") (pin "65") (pinfunction "NC_65") (pintype "passive"))
    )
    (net (code "95") (name "unconnected-(U1C-X0D00-Pad30)") (class "Default")
      (node (ref "U1") (pin "30") (pinfunction "X0D00_30") (pintype "bidirectional"))
    )
    (net (code "96") (name "unconnected-(U1C-X0D02-Pad37)") (class "Default")
      (node (ref "U1") (pin "37") (pinfunction "X0D02_37") (pintype "bidirectional"))
    )
    (net (code "97") (name "unconnected-(U1C-X0D03-Pad38)") (class "Default")
      (node (ref "U1") (pin "38") (pinfunction "X0D03_38") (pintype "bidirectional"))
    )
    (net (code "98") (name "unconnected-(U1C-X0D04-Pad31)") (class "Default")
      (node (ref "U1") (pin "31") (pinfunction "X0D04_31") (pintype "bidirectional"))
    )
    (net (code "99") (name "unconnected-(U1C-X0D05-Pad33)") (class "Default")
      (node (ref "U1") (pin "33") (pinfunction "X0D05_33") (pintype "bidirectional"))
    )
    (net (code "100") (name "unconnected-(U1C-X0D06-Pad34)") (class "Default")
      (node (ref "U1") (pin "34") (pinfunction "X0D06_34") (pintype "bidirectional"))
    )
    (net (code "101") (name "unconnected-(U1C-X0D07-Pad35)") (class "Default")
      (node (ref "U1") (pin "35") (pinfunction "X0D07_35") (pintype "bidirectional"))
    )
    (net (code "102") (name "unconnected-(U1C-X0D08-Pad39)") (class "Default")
      (node (ref "U1") (pin "39") (pinfunction "X0D08_39") (pintype "bidirectional"))
    )
    (net (code "103") (name "unconnected-(U1C-X0D09-Pad40)") (class "Default")
      (node (ref "U1") (pin "40") (pinfunction "X0D09_40") (pintype "bidirectional"))
    )
    (net (code "104") (name "unconnected-(U1C-X0D10-Pad28)") (class "Default")
      (node (ref "U1") (pin "28") (pinfunction "X0D10_28") (pintype "bidirectional"))
    )
    (net (code "105") (name "unconnected-(U1C-X0D11-Pad32)") (class "Default")
      (node (ref "U1") (pin "32") (pinfunction "X0D11_32") (pintype "bidirectional"))
    )
    (net (code "106") (name "unconnected-(U1C-X0D26-Pad93)") (class "Default")
      (node (ref "U1") (pin "93") (pinfunction "X0D26_93") (pintype "bidirectional"))
    )
    (net (code "107") (name "unconnected-(U1C-X0D27-Pad94)") (class "Default")
      (node (ref "U1") (pin "94") (pinfunction "X0D27_94") (pintype "bidirectional"))
    )
    (net (code "108") (name "unconnected-(U1C-X0D28-Pad96)") (class "Default")
      (node (ref "U1") (pin "96") (pinfunction "X0D28_96") (pintype "bidirectional"))
    )
    (net (code "109") (name "unconnected-(U1C-X0D29-Pad98)") (class "Default")
      (node (ref "U1") (pin "98") (pinfunction "X0D29_98") (pintype "bidirectional"))
    )
    (net (code "110") (name "unconnected-(U1C-X0D30-Pad99)") (class "Default")
      (node (ref "U1") (pin "99") (pinfunction "X0D30_99") (pintype "bidirectional"))
    )
    (net (code "111") (name "unconnected-(U1C-X0D31-Pad100)") (class "Default")
      (node (ref "U1") (pin "100") (pinfunction "X0D31_100") (pintype "bidirectional"))
    )
    (net (code "112") (name "unconnected-(U1C-X0D32-Pad95)") (class "Default")
      (node (ref "U1") (pin "95") (pinfunction "X0D32_95") (pintype "bidirectional"))
    )
    (net (code "113") (name "unconnected-(U1C-X0D33-Pad97)") (class "Default")
      (node (ref "U1") (pin "97") (pinfunction "X0D33_97") (pintype "bidirectional"))
    )
    (net (code "114") (name "unconnected-(U1D-X1D02-Pad72)") (class "Default")
      (node (ref "U1") (pin "72") (pinfunction "X1D02_72") (pintype "bidirectional"))
    )
    (net (code "115") (name "unconnected-(U1D-X1D03-Pad74)") (class "Default")
      (node (ref "U1") (pin "74") (pinfunction "X1D03_74") (pintype "bidirectional"))
    )
    (net (code "116") (name "unconnected-(U1D-X1D04-Pad75)") (class "Default")
      (node (ref "U1") (pin "75") (pinfunction "X1D04_75") (pintype "bidirectional"))
    )
    (net (code "117") (name "unconnected-(U1D-X1D05-Pad76)") (class "Default")
      (node (ref "U1") (pin "76") (pinfunction "X1D05_76") (pintype "bidirectional"))
    )
    (net (code "118") (name "unconnected-(U1D-X1D06-Pad77)") (class "Default")
      (node (ref "U1") (pin "77") (pinfunction "X1D06_77") (pintype "bidirectional"))
    )
    (net (code "119") (name "unconnected-(U1D-X1D07-Pad79)") (class "Default")
      (node (ref "U1") (pin "79") (pinfunction "X1D07_79") (pintype "bidirectional"))
    )
    (net (code "120") (name "unconnected-(U1D-X1D08-Pad82)") (class "Default")
      (node (ref "U1") (pin "82") (pinfunction "X1D08_82") (pintype "bidirectional"))
    )
    (net (code "121") (name "unconnected-(U1D-X1D09-Pad84)") (class "Default")
      (node (ref "U1") (pin "84") (pinfunction "X1D09_84") (pintype "bidirectional"))
    )
    (net (code "122") (name "unconnected-(U1D-X1D14-Pad51)") (class "Default")
      (node (ref "U1") (pin "51") (pinfunction "X1D14_51") (pintype "bidirectional"))
    )
    (net (code "123") (name "unconnected-(U1D-X1D15-Pad53)") (class "Default")
      (node (ref "U1") (pin "53") (pinfunction "X1D15_53") (pintype "bidirectional"))
    )
    (net (code "124") (name "unconnected-(U1D-X1D16-Pad22)") (class "Default")
      (node (ref "U1") (pin "22") (pinfunction "X1D16_22") (pintype "bidirectional"))
    )
    (net (code "125") (name "unconnected-(U1D-X1D17-Pad23)") (class "Default")
      (node (ref "U1") (pin "23") (pinfunction "X1D17_23") (pintype "bidirectional"))
    )
    (net (code "126") (name "unconnected-(U1D-X1D18-Pad25)") (class "Default")
      (node (ref "U1") (pin "25") (pinfunction "X1D18_25") (pintype "bidirectional"))
    )
    (net (code "127") (name "unconnected-(U1D-X1D19-Pad26)") (class "Default")
      (node (ref "U1") (pin "26") (pinfunction "X1D19_26") (pintype "bidirectional"))
    )
    (net (code "128") (name "unconnected-(U1D-X1D20-Pad54)") (class "Default")
      (node (ref "U1") (pin "54") (pinfunction "X1D20_54") (pintype "bidirectional"))
    )
    (net (code "129") (name "unconnected-(U1D-X1D21-Pad55)") (class "Default")
      (node (ref "U1") (pin "55") (pinfunction "X1D21_55") (pintype "bidirectional"))
    )
    (net (code "130") (name "unconnected-(U1D-X1D40-Pad106)") (class "Default")
      (node (ref "U1") (pin "106") (pinfunction "X1D40_106") (pintype "bidirectional"))
    )
    (net (code "131") (name "unconnected-(U1D-X1D41-Pad107)") (class "Default")
      (node (ref "U1") (pin "107") (pinfunction "X1D41_107") (pintype "bidirectional"))
    )
    (net (code "132") (name "unconnected-(U1D-X1D42-Pad108)") (class "Default")
      (node (ref "U1") (pin "108") (pinfunction "X1D42_108") (pintype "bidirectional"))
    )
    (net (code "133") (name "unconnected-(U1D-X1D43-Pad109)") (class "Default")
      (node (ref "U1") (pin "109") (pinfunction "X1D43_109") (pintype "bidirectional"))
    )
    (net (code "134") (name "unconnected-(U1E-USB_DM-Pad47)") (class "Default")
      (node (ref "U1") (pin "47") (pinfunction "USB_DM_47") (pintype "bidirectional"))
    )
    (net (code "135") (name "unconnected-(U1E-USB_DP-Pad46)") (class "Default")
      (node (ref "U1") (pin "46") (pinfunction "USB_DP_46") (pintype "bidirectional"))
    )
    (net (code "136") (name "unconnected-(U1E-USB_ID-Pad43)") (class "Default")
      (node (ref "U1") (pin "43") (pinfunction "USB_ID_43") (pintype "passive"))
    )
    (net (code "137") (name "unconnected-(U1E-USB_RTUNE-Pad48)") (class "Default")
      (node (ref "U1") (pin "48") (pinfunction "USB_RTUNE_48") (pintype "passive"))
    )
    (net (code "138") (name "unconnected-(U1E-USB_VBUS-Pad45)") (class "Default")
      (node (ref "U1") (pin "45") (pinfunction "USB_VBUS_45") (pintype "passive"))
    )
    (net (code "139") (name "unconnected-(U5-PG-Pad4)") (class "Default")
      (node (ref "U5") (pin "4") (pinfunction "PG_4") (pintype "passive"))
    )
    (net (code "140") (name "unconnected-(U6-~{MR}-Pad3)") (class "Default")
      (node (ref "U6") (pin "3") (pinfunction "~{MR}_3") (pintype "passive"))
    )
  )
)
